# Power_Delivery.net
KiCad netlist of a schematic drawn in Altium Designer
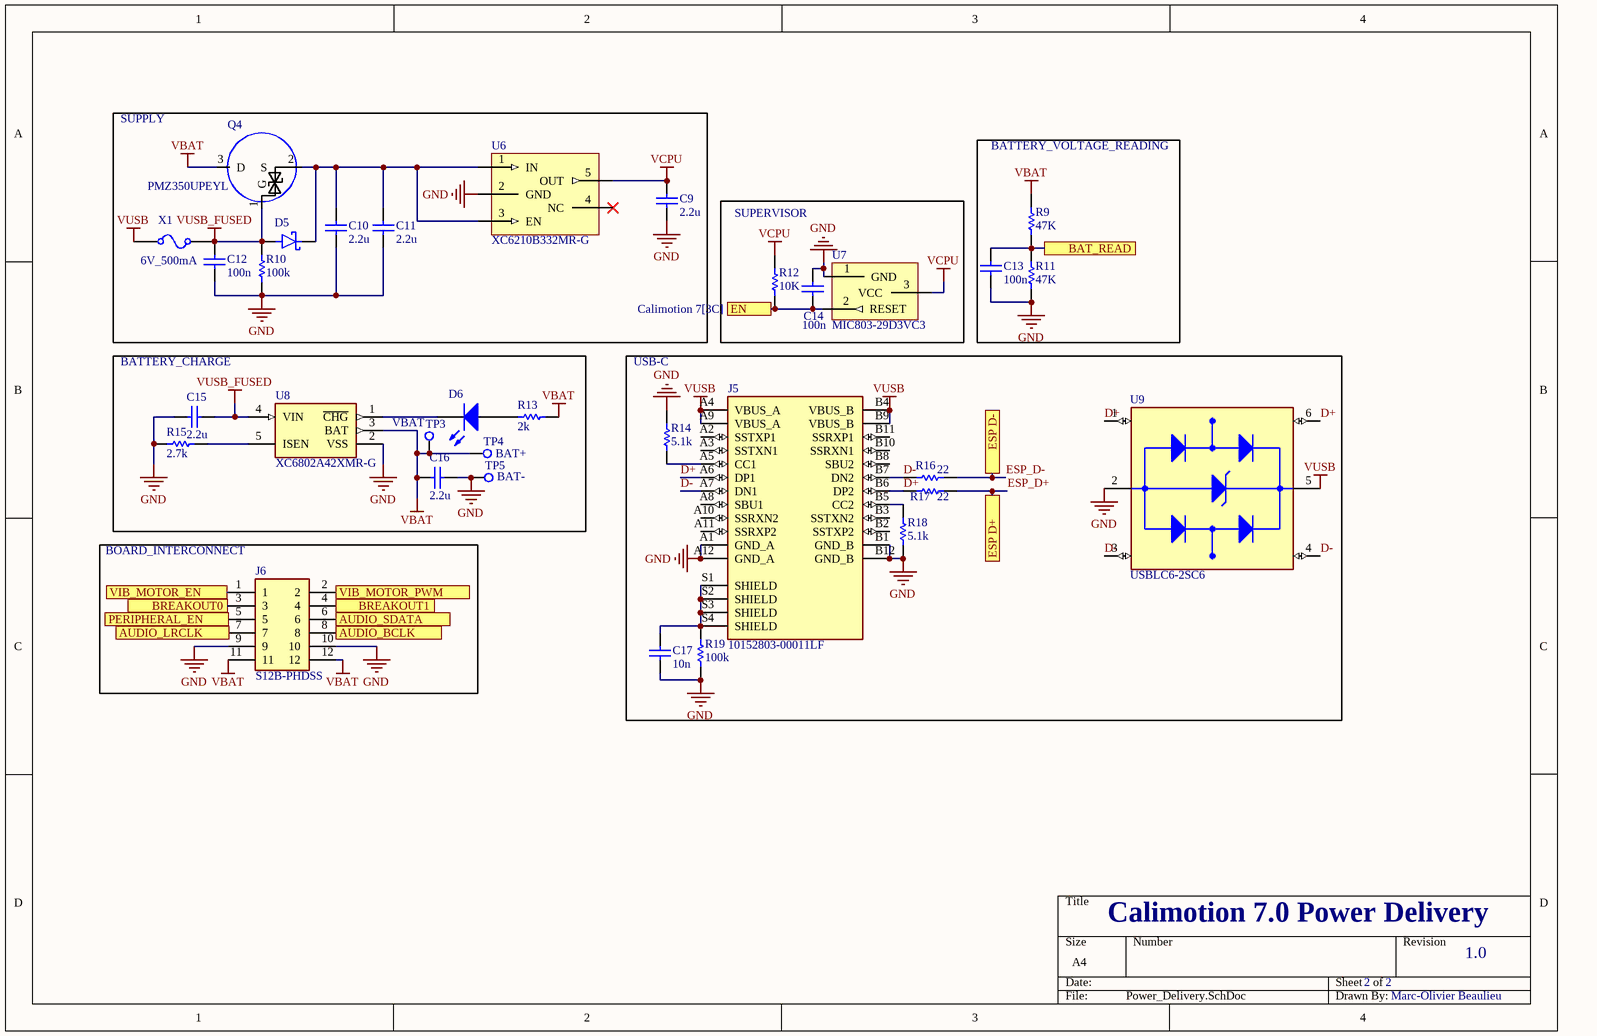
[diagram p0: Power_Delivery.SchDoc]

(export (version "E")
  (design (tool "Eeschema 10.0.6"))
  (components
    (comp (ref "C9")
      (value "2.2u")
      (footprint "CAP 0402_1005")
      (description "Capacitor")
      (libsource (lib "Simulation Generic Components") (part "Capacitor"))
    )
    (comp (ref "C10")
      (value "2.2u")
      (footprint "CAP 0402_1005")
      (description "Capacitor")
      (libsource (lib "Simulation Generic Components") (part "Capacitor"))
    )
    (comp (ref "C11")
      (value "2.2u")
      (footprint "CAP 0402_1005")
      (description "Capacitor")
      (libsource (lib "Simulation Generic Components") (part "Capacitor"))
    )
    (comp (ref "C12")
      (value "100n")
      (footprint "CAP 0402_1005")
      (description "Capacitor")
      (libsource (lib "Simulation Generic Components") (part "Capacitor"))
    )
    (comp (ref "C13")
      (value "100n")
      (footprint "CAP 0402_1005")
      (description "Capacitor")
      (libsource (lib "Simulation Generic Components") (part "Capacitor"))
    )
    (comp (ref "C14")
      (value "100n")
      (footprint "CAP 0402_1005")
      (description "Capacitor")
      (libsource (lib "Simulation Generic Components") (part "Capacitor"))
    )
    (comp (ref "C15")
      (value "2.2u")
      (footprint "CAP 0402_1005")
      (description "Capacitor")
      (libsource (lib "Simulation Generic Components") (part "Capacitor"))
    )
    (comp (ref "C16")
      (value "2.2u")
      (footprint "CAP 0402_1005")
      (description "Capacitor")
      (libsource (lib "Simulation Generic Components") (part "Capacitor"))
    )
    (comp (ref "C17")
      (value "10n")
      (footprint "CAP 0402_1005")
      (description "Capacitor")
      (libsource (lib "Simulation Generic Components") (part "Capacitor"))
    )
    (comp (ref "D5")
      (value "SHOTTKY")
      (footprint "SOD-923")
      (description "Generic Shottky")
      (fields (field (name "MF") "ON Semiconductor") (field (name "MP") "ESD9X5.0ST5G"))
      (libsource (lib "Importred_Components") (part "SHOTTKY"))
    )
    (comp (ref "D6")
      (value "Light-Emitting Diode")
      (footprint "LEDSC160X80X70L45N")
      (libsource (lib "Simulation Generic Components") (part "LED"))
    )
    (comp (ref "J5")
      (value "10152803-00011LF")
      (footprint "AMPHENOL_10152803-00011LF")
      (description "USB 3.2 Type C GEN 2 Receptacle SMT Dual Row 24in")
      (fields (field (name "MF") "Amphenol FCI"))
      (libsource (lib "Importred_Components") (part "10152803-00011LF"))
    )
    (comp (ref "J6")
      (value "S12B-PHDSS")
      (footprint "JST_S12B-PHDSS")
      (description "Connector Header Through Hole, Right Angle 12 position 0.079 _2.00mm_")
      (fields (field (name "MF") "JST Sales") (field (name "MP") "S8B-PHDSS"))
      (libsource (lib "Importred_Components") (part "S12B-PHDSS"))
    )
    (comp (ref "Q4")
      (value "PMZ350UPEYL")
      (footprint "SOT-883")
      (description "P-Channel 20 V 1A (Ta) 360mW (Ta), 3.125W (Tc) Surface Mount SOT-883")
      (libsource (lib "Importred_Components") (part "PMZ350UPEYL"))
    )
    (comp (ref "R9")
      (value "47K")
      (footprint "RES 0402_1005 RF")
      (description "Resistor")
      (libsource (lib "Simulation Generic Components") (part "Resistor"))
    )
    (comp (ref "R10")
      (value "100k")
      (footprint "RES 0402_1005 RF")
      (description "Resistor")
      (libsource (lib "Simulation Generic Components") (part "Resistor"))
    )
    (comp (ref "R11")
      (value "47K")
      (footprint "RES 0402_1005 RF")
      (description "Resistor")
      (libsource (lib "Simulation Generic Components") (part "Resistor"))
    )
    (comp (ref "R12")
      (value "10K")
      (footprint "RES 0402_1005 RF")
      (description "Resistor")
      (libsource (lib "Simulation Generic Components") (part "Resistor"))
    )
    (comp (ref "R13")
      (value "2k")
      (footprint "RES 0402_1005 RF")
      (description "Resistor")
      (libsource (lib "Simulation Generic Components") (part "Resistor"))
    )
    (comp (ref "R14")
      (value "5.1k")
      (footprint "RES 0402_1005 RF")
      (description "Resistor")
      (libsource (lib "Simulation Generic Components") (part "Resistor"))
    )
    (comp (ref "R15")
      (value "2.7k")
      (footprint "RES 0402_1005 RF")
      (description "Resistor")
      (libsource (lib "Simulation Generic Components") (part "Resistor"))
    )
    (comp (ref "R16")
      (value "22")
      (footprint "RES 0402_1005 RF")
      (description "Resistor")
      (libsource (lib "Simulation Generic Components") (part "Resistor"))
    )
    (comp (ref "R17")
      (value "22")
      (footprint "RES 0402_1005 RF")
      (description "Resistor")
      (libsource (lib "Simulation Generic Components") (part "Resistor"))
    )
    (comp (ref "R18")
      (value "5.1k")
      (footprint "RES 0402_1005 RF")
      (description "Resistor")
      (libsource (lib "Simulation Generic Components") (part "Resistor"))
    )
    (comp (ref "R19")
      (value "100k")
      (footprint "RES 0402_1005 RF")
      (description "Resistor")
      (libsource (lib "Simulation Generic Components") (part "Resistor"))
    )
    (comp (ref "TP3")
      (value "VBAT")
      (footprint "THT-Test_Point")
      (libsource (lib "Celestial Library") (part "Test Point"))
    )
    (comp (ref "TP4")
      (value "BAT+")
      (footprint "THT-Test_Point")
      (libsource (lib "Celestial Library") (part "Test Point"))
    )
    (comp (ref "TP5")
      (value "BAT-")
      (footprint "THT-Test_Point")
      (libsource (lib "Celestial Library") (part "Test Point"))
    )
    (comp (ref "U6")
      (value "XC6210B332MR-G")
      (footprint "SOT-25")
      (description "Linear Voltage Regulator IC Positive Fixed 1 Output 700mA SOT-25")
      (libsource (lib "Importred_Components") (part "XC6210B332MR-G"))
    )
    (comp (ref "U7")
      (value "MIC803-29D3VC3")
      (footprint "MIC803-29D3VC3")
      (description "Supervisor Open Drain or Open Collector 1 Channel SC-70-3 Voltage - Threshold 2.93V")
      (libsource (lib "Importred_Components") (part "MIC803-29D3VC3"))
    )
    (comp (ref "U8")
      (value "XC6802A42XMR-G")
      (footprint "SOT-25")
      (description "Charger IC Lithium Ion/Polymer SOT-25")
      (fields (field (name "MF") "Torex"))
      (libsource (lib "Importred_Components") (part "XC6802A42XMR-G"))
    )
    (comp (ref "U9")
      (value "USBLC6-2SC6")
      (footprint "SOT95P280X145-6N")
      (description "17V Clamp 5A (8/20Âµs) Ipp Tvs Diode Surface Mount SOT-23-6")
      (fields (field (name "MF") "STMicroelectronics"))
      (libsource (lib "Importred_Components") (part "USBLC6-2SC6"))
    )
    (comp (ref "X1")
      (value "Fuse")
      (footprint "RES 0402_1005 RF")
      (fields (field (name "CURRENT") "6V_500mA"))
      (libsource (lib "Simulation Generic Components") (part "Fuse"))
    )
  )
  (nets
    (net (code "1") (name "/AUDIO_BCLK") (class "Default")
      (node (ref "J6") (pin "8") (pinfunction "8_8") (pintype "passive"))
    )
    (net (code "2") (name "/AUDIO_LRCLK") (class "Default")
      (node (ref "J6") (pin "7") (pinfunction "7_7") (pintype "passive"))
    )
    (net (code "3") (name "/AUDIO_SDATA") (class "Default")
      (node (ref "J6") (pin "6") (pinfunction "6_6") (pintype "passive"))
    )
    (net (code "4") (name "/BAT_READ") (class "Default")
      (node (ref "C13") (pin "1") (pinfunction "1_1") (pintype "passive"))
      (node (ref "R11") (pin "1") (pinfunction "1_1") (pintype "passive"))
      (node (ref "R9") (pin "2") (pinfunction "2_2") (pintype "passive"))
    )
    (net (code "5") (name "/BREAKOUT0") (class "Default")
      (node (ref "J6") (pin "3") (pinfunction "3_3") (pintype "passive"))
    )
    (net (code "6") (name "/BREAKOUT1") (class "Default")
      (node (ref "J6") (pin "4") (pinfunction "4_4") (pintype "passive"))
    )
    (net (code "7") (name "/D+") (class "Default")
      (node (ref "J5") (pin "A6") (pinfunction "DP1_A6") (pintype "bidirectional"))
      (node (ref "J5") (pin "B6") (pinfunction "DP2_B6") (pintype "bidirectional"))
      (node (ref "R17") (pin "1") (pinfunction "1_1") (pintype "passive"))
      (node (ref "U9") (pin "1") (pinfunction "I/O1_IN_1") (pintype "bidirectional"))
      (node (ref "U9") (pin "6") (pinfunction "I/O1_OUT_6") (pintype "bidirectional"))
    )
    (net (code "8") (name "/D-") (class "Default")
      (node (ref "J5") (pin "A7") (pinfunction "DN1_A7") (pintype "bidirectional"))
      (node (ref "J5") (pin "B7") (pinfunction "DN2_B7") (pintype "bidirectional"))
      (node (ref "R16") (pin "1") (pinfunction "1_1") (pintype "passive"))
      (node (ref "U9") (pin "3") (pinfunction "I/O2_IN_3") (pintype "bidirectional"))
      (node (ref "U9") (pin "4") (pinfunction "I/O2_OUT_4") (pintype "bidirectional"))
    )
    (net (code "9") (name "/EN") (class "Default")
      (node (ref "C14") (pin "2") (pinfunction "2_2") (pintype "passive"))
      (node (ref "R12") (pin "1") (pinfunction "1_1") (pintype "passive"))
      (node (ref "U7") (pin "2") (pinfunction "RESET_2") (pintype "output"))
    )
    (net (code "10") (name "/ESP_D+") (class "Default")
      (node (ref "R17") (pin "2") (pinfunction "2_2") (pintype "passive"))
    )
    (net (code "11") (name "/ESP_D-") (class "Default")
      (node (ref "R16") (pin "2") (pinfunction "2_2") (pintype "passive"))
    )
    (net (code "12") (name "/PERIPHERAL_EN") (class "Default")
      (node (ref "J6") (pin "5") (pinfunction "5_5") (pintype "passive"))
    )
    (net (code "13") (name "/VIB_MOTOR_EN") (class "Default")
      (node (ref "J6") (pin "1") (pinfunction "1_1") (pintype "passive"))
    )
    (net (code "14") (name "/VIB_MOTOR_PWM") (class "Default")
      (node (ref "J6") (pin "2") (pinfunction "2_2") (pintype "passive"))
    )
    (net (code "15") (name "GND") (class "Default")
      (node (ref "C10") (pin "2") (pinfunction "2_2") (pintype "passive"))
      (node (ref "C11") (pin "2") (pinfunction "2_2") (pintype "passive"))
      (node (ref "C12") (pin "1") (pinfunction "1_1") (pintype "passive"))
      (node (ref "C13") (pin "2") (pinfunction "2_2") (pintype "passive"))
      (node (ref "C14") (pin "1") (pinfunction "1_1") (pintype "passive"))
      (node (ref "C15") (pin "2") (pinfunction "2_2") (pintype "passive"))
      (node (ref "C16") (pin "1") (pinfunction "1_1") (pintype "passive"))
      (node (ref "C17") (pin "2") (pinfunction "2_2") (pintype "passive"))
      (node (ref "C9") (pin "1") (pinfunction "1_1") (pintype "passive"))
      (node (ref "J5") (pin "A1") (pinfunction "GND_A_A1") (pintype "power_in"))
      (node (ref "J5") (pin "A12") (pinfunction "GND_A_A12") (pintype "power_in"))
      (node (ref "J5") (pin "B1") (pinfunction "GND_B_B1") (pintype "power_in"))
      (node (ref "J5") (pin "B12") (pinfunction "GND_B_B12") (pintype "power_in"))
      (node (ref "J6") (pin "10") (pinfunction "10_10") (pintype "passive"))
      (node (ref "J6") (pin "9") (pinfunction "9_9") (pintype "passive"))
      (node (ref "R10") (pin "2") (pinfunction "2_2") (pintype "passive"))
      (node (ref "R11") (pin "2") (pinfunction "2_2") (pintype "passive"))
      (node (ref "R14") (pin "2") (pinfunction "2_2") (pintype "passive"))
      (node (ref "R15") (pin "2") (pinfunction "2_2") (pintype "passive"))
      (node (ref "R18") (pin "1") (pinfunction "1_1") (pintype "passive"))
      (node (ref "R19") (pin "2") (pinfunction "2_2") (pintype "passive"))
      (node (ref "TP5") (pin "1") (pinfunction "TP_1") (pintype "passive"))
      (node (ref "U6") (pin "2") (pinfunction "GND_2") (pintype "power_in"))
      (node (ref "U7") (pin "1") (pinfunction "GND_1") (pintype "power_in"))
      (node (ref "U8") (pin "2") (pinfunction "VSS_2") (pintype "power_in"))
      (node (ref "U9") (pin "2") (pinfunction "GND_2") (pintype "power_in"))
    )
    (net (code "16") (name "Net-(C17-Pad1)") (class "Default")
      (node (ref "C17") (pin "1") (pinfunction "1_1") (pintype "passive"))
      (node (ref "J5") (pin "S1") (pinfunction "SHIELD_S1") (pintype "passive"))
      (node (ref "J5") (pin "S2") (pinfunction "SHIELD_S2") (pintype "passive"))
      (node (ref "J5") (pin "S3") (pinfunction "SHIELD_S3") (pintype "passive"))
      (node (ref "J5") (pin "S4") (pinfunction "SHIELD_S4") (pintype "passive"))
      (node (ref "R19") (pin "1") (pinfunction "1_1") (pintype "passive"))
    )
    (net (code "17") (name "Net-(D5-K)") (class "Default")
      (node (ref "C10") (pin "1") (pinfunction "1_1") (pintype "passive"))
      (node (ref "C11") (pin "1") (pinfunction "1_1") (pintype "passive"))
      (node (ref "D5") (pin "C") (pinfunction "K_C") (pintype "passive"))
      (node (ref "Q4") (pin "2") (pinfunction "S_2") (pintype "passive"))
      (node (ref "U6") (pin "1") (pinfunction "IN_1") (pintype "input"))
      (node (ref "U6") (pin "3") (pinfunction "EN_3") (pintype "input"))
    )
    (net (code "18") (name "Net-(D6-A)") (class "Default")
      (node (ref "D6") (pin "1") (pinfunction "A_1") (pintype "passive"))
      (node (ref "R13") (pin "2") (pinfunction "2_2") (pintype "passive"))
    )
    (net (code "19") (name "Net-(D6-K)") (class "Default")
      (node (ref "D6") (pin "2") (pinfunction "K_2") (pintype "passive"))
      (node (ref "U8") (pin "1") (pinfunction "~{CHG}_1") (pintype "output"))
    )
    (net (code "20") (name "Net-(J5-CC1)") (class "Default")
      (node (ref "J5") (pin "A5") (pinfunction "CC1_A5") (pintype "bidirectional"))
      (node (ref "R14") (pin "1") (pinfunction "1_1") (pintype "passive"))
    )
    (net (code "21") (name "Net-(J5-CC2)") (class "Default")
      (node (ref "J5") (pin "B5") (pinfunction "CC2_B5") (pintype "bidirectional"))
      (node (ref "R18") (pin "2") (pinfunction "2_2") (pintype "passive"))
    )
    (net (code "22") (name "Net-(U8-ISEN)") (class "Default")
      (node (ref "R15") (pin "1") (pinfunction "1_1") (pintype "passive"))
      (node (ref "U8") (pin "5") (pinfunction "ISEN_5") (pintype "passive"))
    )
    (net (code "23") (name "VBAT") (class "Default")
      (node (ref "C16") (pin "2") (pinfunction "2_2") (pintype "passive"))
      (node (ref "J6") (pin "11") (pinfunction "11_11") (pintype "passive"))
      (node (ref "J6") (pin "12") (pinfunction "12_12") (pintype "passive"))
      (node (ref "Q4") (pin "3") (pinfunction "D_3") (pintype "passive"))
      (node (ref "R13") (pin "1") (pinfunction "1_1") (pintype "passive"))
      (node (ref "R9") (pin "1") (pinfunction "1_1") (pintype "passive"))
      (node (ref "TP3") (pin "1") (pinfunction "TP_1") (pintype "passive"))
      (node (ref "TP4") (pin "1") (pinfunction "TP_1") (pintype "passive"))
      (node (ref "U8") (pin "3") (pinfunction "BAT_3") (pintype "output"))
    )
    (net (code "24") (name "VCPU") (class "Default")
      (node (ref "C9") (pin "2") (pinfunction "2_2") (pintype "passive"))
      (node (ref "R12") (pin "2") (pinfunction "2_2") (pintype "passive"))
      (node (ref "U6") (pin "5") (pinfunction "OUT_5") (pintype "output"))
      (node (ref "U7") (pin "3") (pinfunction "VCC_3") (pintype "power_in"))
    )
    (net (code "25") (name "VUSB") (class "Default")
      (node (ref "J5") (pin "A4") (pinfunction "VBUS_A_A4") (pintype "power_in"))
      (node (ref "J5") (pin "A9") (pinfunction "VBUS_A_A9") (pintype "power_in"))
      (node (ref "J5") (pin "B4") (pinfunction "VBUS_B_B4") (pintype "power_in"))
      (node (ref "J5") (pin "B9") (pinfunction "VBUS_B_B9") (pintype "power_in"))
      (node (ref "U9") (pin "5") (pinfunction "VBUS_5") (pintype "power_in"))
      (node (ref "X1") (pin "1") (pinfunction "1_1") (pintype "passive"))
    )
    (net (code "26") (name "VUSB_FUSED") (class "Default")
      (node (ref "C12") (pin "2") (pinfunction "2_2") (pintype "passive"))
      (node (ref "C15") (pin "1") (pinfunction "1_1") (pintype "passive"))
      (node (ref "D5") (pin "A") (pinfunction "A_A") (pintype "passive"))
      (node (ref "Q4") (pin "1") (pinfunction "G_1") (pintype "passive"))
      (node (ref "R10") (pin "1") (pinfunction "1_1") (pintype "passive"))
      (node (ref "U8") (pin "4") (pinfunction "VIN_4") (pintype "input"))
      (node (ref "X1") (pin "2") (pinfunction "2_2") (pintype "passive"))
    )
    (net (code "27") (name "unconnected-(J5-SBU1-PadA8)") (class "Default")
      (node (ref "J5") (pin "A8") (pinfunction "SBU1_A8") (pintype "bidirectional"))
    )
    (net (code "28") (name "unconnected-(J5-SBU2-PadB8)") (class "Default")
      (node (ref "J5") (pin "B8") (pinfunction "SBU2_B8") (pintype "bidirectional"))
    )
    (net (code "29") (name "unconnected-(J5-SSRXN1-PadB10)") (class "Default")
      (node (ref "J5") (pin "B10") (pinfunction "SSRXN1_B10") (pintype "bidirectional"))
    )
    (net (code "30") (name "unconnected-(J5-SSRXN2-PadA10)") (class "Default")
      (node (ref "J5") (pin "A10") (pinfunction "SSRXN2_A10") (pintype "bidirectional"))
    )
    (net (code "31") (name "unconnected-(J5-SSRXP1-PadB11)") (class "Default")
      (node (ref "J5") (pin "B11") (pinfunction "SSRXP1_B11") (pintype "bidirectional"))
    )
    (net (code "32") (name "unconnected-(J5-SSRXP2-PadA11)") (class "Default")
      (node (ref "J5") (pin "A11") (pinfunction "SSRXP2_A11") (pintype "bidirectional"))
    )
    (net (code "33") (name "unconnected-(J5-SSTXN1-PadA3)") (class "Default")
      (node (ref "J5") (pin "A3") (pinfunction "SSTXN1_A3") (pintype "bidirectional"))
    )
    (net (code "34") (name "unconnected-(J5-SSTXN2-PadB3)") (class "Default")
      (node (ref "J5") (pin "B3") (pinfunction "SSTXN2_B3") (pintype "bidirectional"))
    )
    (net (code "35") (name "unconnected-(J5-SSTXP1-PadA2)") (class "Default")
      (node (ref "J5") (pin "A2") (pinfunction "SSTXP1_A2") (pintype "bidirectional"))
    )
    (net (code "36") (name "unconnected-(J5-SSTXP2-PadB2)") (class "Default")
      (node (ref "J5") (pin "B2") (pinfunction "SSTXP2_B2") (pintype "bidirectional"))
    )
    (net (code "37") (name "unconnected-(U6-NC-Pad4)") (class "Default")
      (node (ref "U6") (pin "4") (pinfunction "NC_4") (pintype "passive+no_connect"))
    )
  )
)
